# Power_5V_Rev1_1.net
KiCad netlist of a schematic drawn in Altium Designer
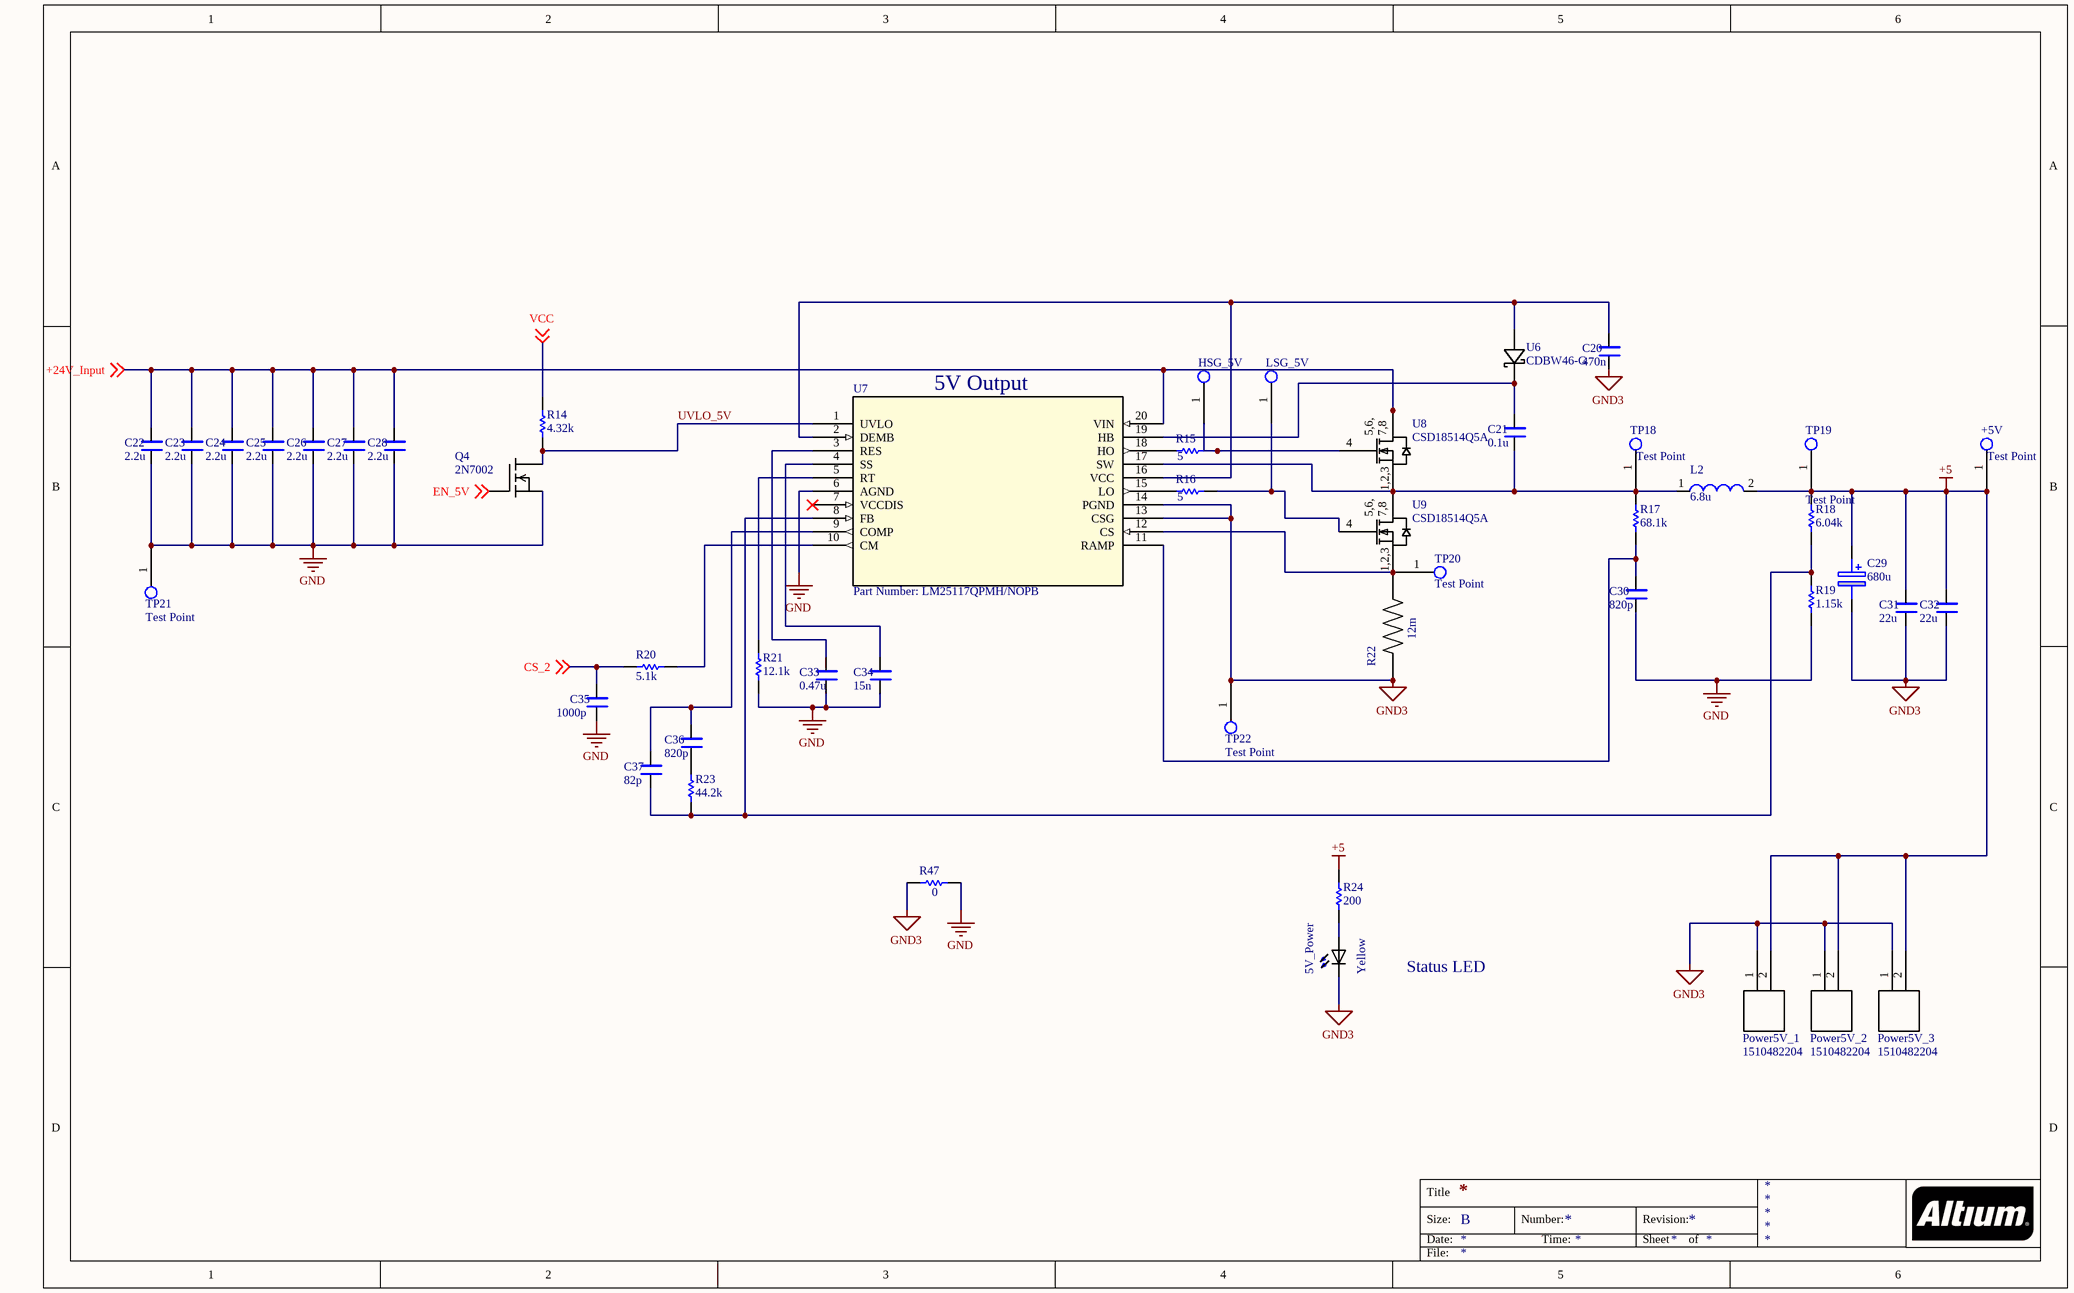
[diagram p0: Power_5V_Rev1.1.SchDoc]

(export (version "E")
  (design (tool "Eeschema 10.0.6"))
  (components
    (comp (ref "+5V")
      (value "Test Point")
      (footprint "Test Point Through-hole")
      (libsource (lib "Test Points") (part "Test Point"))
    )
    (comp (ref "5V_Power")
      (value "Yellow")
      (footprint "*DIOC200X125X110_LTST-C171KSKT(Primary)")
      (description "Yellow 2 x 1.25 x 0.8 mm 130Â° Water Clear 50 mcd 2 V LED SMT")
      (fields (field (name "MP") "LTST-C171KSKT") (field (name "DIGI-KEY_PART_NUMBER") "160-1428-1-ND"))
      (libsource (lib "LTST-C171KSKT") (part "LTST-C171KSKT"))
    )
    (comp (ref "C20")
      (value "470n")
      (footprint "*CAPC2012X88N")
      (description "100pF Â±5% 250V Ceramic Capacitor C0G, NP0 0805 _2012 Metric_")
      (fields (field (name "MF") "KEMET") (field (name "DIGI-KEY_PART_NUMBER") "399-15000-1-ND"))
      (libsource (lib "C0805C101JAGAC7800") (part "C0805C101JAGAC7800"))
    )
    (comp (ref "C21")
      (value "0.1u")
      (footprint "*CAPC2012X88N")
      (description "100pF Â±5% 250V Ceramic Capacitor C0G, NP0 0805 _2012 Metric_")
      (fields (field (name "MF") "KEMET") (field (name "DIGI-KEY_PART_NUMBER") "399-15000-1-ND"))
      (libsource (lib "C0805C101JAGAC7800") (part "C0805C101JAGAC7800"))
    )
    (comp (ref "C22")
      (value "2.2u")
      (footprint "*CAPC2012X88N")
      (description "100pF Â±5% 250V Ceramic Capacitor C0G, NP0 0805 _2012 Metric_")
      (fields (field (name "MF") "KEMET") (field (name "DIGI-KEY_PART_NUMBER") "399-15000-1-ND"))
      (libsource (lib "C0805C101JAGAC7800") (part "C0805C101JAGAC7800"))
    )
    (comp (ref "C23")
      (value "2.2u")
      (footprint "*CAPC2012X88N")
      (description "100pF Â±5% 250V Ceramic Capacitor C0G, NP0 0805 _2012 Metric_")
      (fields (field (name "MF") "KEMET") (field (name "DIGI-KEY_PART_NUMBER") "399-15000-1-ND"))
      (libsource (lib "C0805C101JAGAC7800") (part "C0805C101JAGAC7800"))
    )
    (comp (ref "C24")
      (value "2.2u")
      (footprint "*CAPC2012X88N")
      (description "100pF Â±5% 250V Ceramic Capacitor C0G, NP0 0805 _2012 Metric_")
      (fields (field (name "MF") "KEMET") (field (name "DIGI-KEY_PART_NUMBER") "399-15000-1-ND"))
      (libsource (lib "C0805C101JAGAC7800") (part "C0805C101JAGAC7800"))
    )
    (comp (ref "C25")
      (value "2.2u")
      (footprint "*CAPC2012X88N")
      (description "100pF Â±5% 250V Ceramic Capacitor C0G, NP0 0805 _2012 Metric_")
      (fields (field (name "MF") "KEMET") (field (name "DIGI-KEY_PART_NUMBER") "399-15000-1-ND"))
      (libsource (lib "C0805C101JAGAC7800") (part "C0805C101JAGAC7800"))
    )
    (comp (ref "C26")
      (value "2.2u")
      (footprint "*CAPC2012X88N")
      (description "100pF Â±5% 250V Ceramic Capacitor C0G, NP0 0805 _2012 Metric_")
      (fields (field (name "MF") "KEMET") (field (name "DIGI-KEY_PART_NUMBER") "399-15000-1-ND"))
      (libsource (lib "C0805C101JAGAC7800") (part "C0805C101JAGAC7800"))
    )
    (comp (ref "C27")
      (value "2.2u")
      (footprint "*CAPC2012X88N")
      (description "100pF Â±5% 250V Ceramic Capacitor C0G, NP0 0805 _2012 Metric_")
      (fields (field (name "MF") "KEMET") (field (name "DIGI-KEY_PART_NUMBER") "399-15000-1-ND"))
      (libsource (lib "C0805C101JAGAC7800") (part "C0805C101JAGAC7800"))
    )
    (comp (ref "C28")
      (value "2.2u")
      (footprint "*CAPC2012X88N")
      (description "100pF Â±5% 250V Ceramic Capacitor C0G, NP0 0805 _2012 Metric_")
      (fields (field (name "MF") "KEMET") (field (name "DIGI-KEY_PART_NUMBER") "399-15000-1-ND"))
      (libsource (lib "C0805C101JAGAC7800") (part "C0805C101JAGAC7800"))
    )
    (comp (ref "C29")
      (value "680u")
      (footprint "CAPPRD500W65D1000H1800")
      (fields
        (field (name "MANUFACTURER_PART_NUMBER") "EEUFC1V331")
        (field (name "RS PART NUMBER") "1081337")
      )
      (libsource (lib "Power Distribution") (part "EEUFC1V331"))
    )
    (comp (ref "C30")
      (value "820p")
      (footprint "*CAPC2012X88N")
      (description "100pF Â±5% 250V Ceramic Capacitor C0G, NP0 0805 _2012 Metric_")
      (fields (field (name "MF") "KEMET") (field (name "DIGI-KEY_PART_NUMBER") "399-15000-1-ND"))
      (libsource (lib "C0805C101JAGAC7800") (part "C0805C101JAGAC7800"))
    )
    (comp (ref "C31")
      (value "22u")
      (footprint "*CAPC2012X88N")
      (description "100pF Â±5% 250V Ceramic Capacitor C0G, NP0 0805 _2012 Metric_")
      (fields (field (name "MF") "KEMET") (field (name "DIGI-KEY_PART_NUMBER") "399-15000-1-ND"))
      (libsource (lib "C0805C101JAGAC7800") (part "C0805C101JAGAC7800"))
    )
    (comp (ref "C32")
      (value "22u")
      (footprint "*CAPC2012X88N")
      (description "100pF Â±5% 250V Ceramic Capacitor C0G, NP0 0805 _2012 Metric_")
      (fields (field (name "MF") "KEMET") (field (name "DIGI-KEY_PART_NUMBER") "399-15000-1-ND"))
      (libsource (lib "C0805C101JAGAC7800") (part "C0805C101JAGAC7800"))
    )
    (comp (ref "C33")
      (value "0.47u")
      (footprint "*CAPC2012X88N")
      (description "100pF Â±5% 250V Ceramic Capacitor C0G, NP0 0805 _2012 Metric_")
      (fields (field (name "MF") "KEMET") (field (name "DIGI-KEY_PART_NUMBER") "399-15000-1-ND"))
      (libsource (lib "C0805C101JAGAC7800") (part "C0805C101JAGAC7800"))
    )
    (comp (ref "C34")
      (value "15n")
      (footprint "*CAPC2012X88N")
      (description "100pF Â±5% 250V Ceramic Capacitor C0G, NP0 0805 _2012 Metric_")
      (fields (field (name "MF") "KEMET") (field (name "DIGI-KEY_PART_NUMBER") "399-15000-1-ND"))
      (libsource (lib "C0805C101JAGAC7800") (part "C0805C101JAGAC7800"))
    )
    (comp (ref "C35")
      (value "1000p")
      (footprint "*CAPC2012X88N")
      (description "100pF Â±5% 250V Ceramic Capacitor C0G, NP0 0805 _2012 Metric_")
      (fields (field (name "MF") "KEMET") (field (name "DIGI-KEY_PART_NUMBER") "399-15000-1-ND"))
      (libsource (lib "C0805C101JAGAC7800") (part "C0805C101JAGAC7800"))
    )
    (comp (ref "C36")
      (value "820p")
      (footprint "*CAPC2012X88N")
      (description "100pF Â±5% 250V Ceramic Capacitor C0G, NP0 0805 _2012 Metric_")
      (fields (field (name "MF") "KEMET") (field (name "DIGI-KEY_PART_NUMBER") "399-15000-1-ND"))
      (libsource (lib "C0805C101JAGAC7800") (part "C0805C101JAGAC7800"))
    )
    (comp (ref "C37")
      (value "82p")
      (footprint "*CAPC2012X88N")
      (description "100pF Â±5% 250V Ceramic Capacitor C0G, NP0 0805 _2012 Metric_")
      (fields (field (name "MF") "KEMET") (field (name "DIGI-KEY_PART_NUMBER") "399-15000-1-ND"))
      (libsource (lib "C0805C101JAGAC7800") (part "C0805C101JAGAC7800"))
    )
    (comp (ref "HSG_5V")
      (value "~")
      (footprint "Test Point Through-hole")
      (libsource (lib "Test Points") (part "Test Point"))
    )
    (comp (ref "L2")
      (value "6.8u")
      (footprint "XAL1010-682")
      (description "Power inductor, high current, 10% tol, SMT, RoHS")
      (fields (field (name "MF") "Coilcraft") (field (name "MP") "SER2915H-153KL"))
      (libsource (lib "SER2915H-153KL") (part "SER2915H-153KL"))
    )
    (comp (ref "LSG_5V")
      (value "~")
      (footprint "Test Point Through-hole")
      (libsource (lib "Test Points") (part "Test Point"))
    )
    (comp (ref "Power5V_1")
      (value "1510482204")
      (footprint "1510482204")
      (description "Molex 6.5MM 2 pin connector, used for power connections. P/N 1510482204 and similar models.")
      (libsource (lib "Power Distribution") (part "1510482204"))
    )
    (comp (ref "Power5V_2")
      (value "1510482204")
      (footprint "1510482204")
      (description "Molex 6.5MM 2 pin connector, used for power connections. P/N 1510482204 and similar models.")
      (libsource (lib "Power Distribution") (part "1510482204"))
    )
    (comp (ref "Power5V_3")
      (value "1510482204")
      (footprint "1510482204")
      (description "Molex 6.5MM 2 pin connector, used for power connections. P/N 1510482204 and similar models.")
      (libsource (lib "Power Distribution") (part "1510482204"))
    )
    (comp (ref "Q4")
      (value "2N7002")
      (footprint "*SOT23")
      (description "Trans MOSFET N-CH 60V 0.115A 3-Pin SOT-23 T/R")
      (fields (field (name "MF") "ON Semiconductor"))
      (libsource (lib "2N7002") (part "2N7002"))
    )
    (comp (ref "R14")
      (value "4.32k")
      (footprint "RESC0805(2012)_M")
      (description "8M06 0.125W 1% 0805 (2012 Metric)  SMD")
      (fields (field (name "POWER") "0.125 W") (field (name "TOLERANCE") "1 %"))
      (libsource (lib "Altium Content Vault") (part "RES"))
    )
    (comp (ref "R15")
      (value "5")
      (footprint "AXIAL-0.3")
      (description "120R 0.125W 5% 0805 (2012 Metric)  SMD")
      (fields (field (name "TOLERANCE") "5 %") (field (name "POWER") "0.125 W"))
      (libsource (lib "Power Distribution") (part "120R 5% 0805"))
    )
    (comp (ref "R16")
      (value "5")
      (footprint "AXIAL-0.3")
      (description "120R 0.125W 5% 0805 (2012 Metric)  SMD")
      (fields (field (name "TOLERANCE") "5 %") (field (name "POWER") "0.125 W"))
      (libsource (lib "Power Distribution") (part "120R 5% 0805"))
    )
    (comp (ref "R17")
      (value "68.1k")
      (footprint "RESC0805(2012)_M")
      (description "8M06 0.125W 1% 0805 (2012 Metric)  SMD")
      (fields (field (name "POWER") "0.125 W") (field (name "TOLERANCE") "1 %"))
      (libsource (lib "Altium Content Vault") (part "RES"))
    )
    (comp (ref "R18")
      (value "6.04k")
      (footprint "RESC0805(2012)_M")
      (description "8M06 0.125W 1% 0805 (2012 Metric)  SMD")
      (fields (field (name "POWER") "0.125 W") (field (name "TOLERANCE") "1 %"))
      (libsource (lib "Altium Content Vault") (part "RES"))
    )
    (comp (ref "R19")
      (value "1.15k")
      (footprint "RESC0805(2012)_M")
      (description "8M06 0.125W 1% 0805 (2012 Metric)  SMD")
      (fields (field (name "POWER") "0.125 W") (field (name "TOLERANCE") "1 %"))
      (libsource (lib "Altium Content Vault") (part "RES"))
    )
    (comp (ref "R20")
      (value "5.1k")
      (footprint "RESC0805(2012)_M")
      (description "8M06 0.125W 1% 0805 (2012 Metric)  SMD")
      (fields (field (name "POWER") "0.125 W") (field (name "TOLERANCE") "1 %"))
      (libsource (lib "Altium Content Vault") (part "RES"))
    )
    (comp (ref "R21")
      (value "12.1k")
      (footprint "RESC0805(2012)_M")
      (description "8M06 0.125W 1% 0805 (2012 Metric)  SMD")
      (fields (field (name "POWER") "0.125 W") (field (name "TOLERANCE") "1 %"))
      (libsource (lib "Altium Content Vault") (part "RES"))
    )
    (comp (ref "R22")
      (value "12m")
      (footprint "*RESC6432X110N")
      (description "Res Thick Film 2512 0.012 Ohm 1% 1W Pad SMD Automotive T/R")
      (fields (field (name "MP") "ERJ-M1WSF12MU") (field (name "DIGI-KEY_PART_NUMBER") "P12MCT-ND"))
      (libsource (lib "ERJ-M1WSF12MU") (part "ERJ-M1WSF12MU"))
    )
    (comp (ref "R23")
      (value "44.2k")
      (footprint "RESC0805(2012)_M")
      (description "8M06 0.125W 1% 0805 (2012 Metric)  SMD")
      (fields (field (name "POWER") "0.125 W") (field (name "TOLERANCE") "1 %"))
      (libsource (lib "Altium Content Vault") (part "RES"))
    )
    (comp (ref "R24")
      (value "200")
      (footprint "RESC0805(2012)_M")
      (description "8M06 0.125W 1% 0805 (2012 Metric)  SMD")
      (fields (field (name "POWER") "0.125 W") (field (name "TOLERANCE") "1 %"))
      (libsource (lib "Altium Content Vault") (part "RES"))
    )
    (comp (ref "R47")
      (value "0")
      (footprint "RESC0805(2012)_M")
      (description "8M06 0.125W 1% 0805 (2012 Metric)  SMD")
      (fields (field (name "POWER") "0.125 W") (field (name "TOLERANCE") "1 %"))
      (libsource (lib "Altium Content Vault") (part "RES"))
    )
    (comp (ref "TP18")
      (value "Test Point")
      (footprint "Test Point Through-hole")
      (libsource (lib "Test Points") (part "Test Point"))
    )
    (comp (ref "TP19")
      (value "Test Point")
      (footprint "Test Point Through-hole")
      (libsource (lib "Test Points") (part "Test Point"))
    )
    (comp (ref "TP20")
      (value "Test Point")
      (footprint "Test Point Through-hole")
      (libsource (lib "Test Points") (part "Test Point"))
    )
    (comp (ref "TP21")
      (value "Test Point")
      (footprint "Test Point Through-hole")
      (libsource (lib "Test Points") (part "Test Point"))
    )
    (comp (ref "TP22")
      (value "Test Point")
      (footprint "Test Point Through-hole")
      (libsource (lib "Test Points") (part "Test Point"))
    )
    (comp (ref "U6")
      (value "CDBW46-G")
      (footprint "CDBW")
      (description "No Description Available")
      (fields (field (name "COPYRIGHT") "Copyright (C) 2018 Accelerated Designs. All rights reserved"))
      (libsource (lib "DIODE SCHOTTKY 100V 150MA") (part "CDBW46-G"))
    )
    (comp (ref "U7")
      (value "Part Number: LM25117QPMH/NOPB")
      (footprint "MXA20A")
      (description "No Description Available")
      (fields
        (field (name "MANUFACTURER") "Texas Instruments")
        (field (name "MANUFACTURER_PART_NUMBER") "LM25117QPMH/NOPB")
        (field (name "COPYRIGHT") "Copyright (C) 2018 Accelerated Designs. All rights reserved")
      )
      (libsource (lib "2019-11-16_22-35-15") (part "LM25117QPMH/NOPB"))
    )
    (comp (ref "U8")
      (value "CSD18514Q5A")
      (footprint "DQJ0008A")
      (description "No Description Available")
      (fields (field (name "COPYRIGHT") "Copyright (C) 2018 Accelerated Designs. All rights reserved"))
      (libsource (lib "ul_CSD18514Q5A") (part "CSD18514Q5A"))
    )
    (comp (ref "U9")
      (value "CSD18514Q5A")
      (footprint "DQJ0008A")
      (description "No Description Available")
      (fields (field (name "COPYRIGHT") "Copyright (C) 2018 Accelerated Designs. All rights reserved"))
      (libsource (lib "ul_CSD18514Q5A") (part "CSD18514Q5A"))
    )
  )
  (nets
    (net (code "1") (name "+5") (class "Default")
      (node (ref "+5V") (pin "1") (pinfunction "1_1") (pintype "passive"))
      (node (ref "C29") (pin "1") (pinfunction "+_1") (pintype "passive"))
      (node (ref "C31") (pin "2") (pinfunction "2_2") (pintype "passive"))
      (node (ref "C32") (pin "2") (pinfunction "2_2") (pintype "passive"))
      (node (ref "L2") (pin "2") (pinfunction "2_2") (pintype "passive"))
      (node (ref "Power5V_1") (pin "2") (pintype "passive"))
      (node (ref "Power5V_2") (pin "2") (pintype "passive"))
      (node (ref "Power5V_3") (pin "2") (pintype "passive"))
      (node (ref "R18") (pin "2") (pinfunction "2_2") (pintype "passive"))
      (node (ref "R24") (pin "2") (pinfunction "2_2") (pintype "passive"))
      (node (ref "TP19") (pin "1") (pinfunction "1_1") (pintype "passive"))
    )
    (net (code "2") (name "+24V_Input") (class "Default")
      (node (ref "C22") (pin "2") (pinfunction "2_2") (pintype "passive"))
      (node (ref "C23") (pin "2") (pinfunction "2_2") (pintype "passive"))
      (node (ref "C24") (pin "2") (pinfunction "2_2") (pintype "passive"))
      (node (ref "C25") (pin "2") (pinfunction "2_2") (pintype "passive"))
      (node (ref "C26") (pin "2") (pinfunction "2_2") (pintype "passive"))
      (node (ref "C27") (pin "2") (pinfunction "2_2") (pintype "passive"))
      (node (ref "C28") (pin "2") (pinfunction "2_2") (pintype "passive"))
      (node (ref "U7") (pin "20") (pinfunction "VIN_20") (pintype "input"))
      (node (ref "U8") (pin "5") (pinfunction "D_5") (pintype "passive"))
      (node (ref "U8") (pin "6") (pinfunction "D_6") (pintype "passive"))
      (node (ref "U8") (pin "7") (pinfunction "D_7") (pintype "passive"))
      (node (ref "U8") (pin "8") (pinfunction "D_8") (pintype "passive"))
    )
    (net (code "3") (name "/UVLO_5V") (class "Default")
      (node (ref "Q4") (pin "3") (pinfunction "D_3") (pintype "passive"))
      (node (ref "R14") (pin "1") (pinfunction "1_1") (pintype "passive"))
      (node (ref "U7") (pin "1") (pinfunction "UVLO_1") (pintype "passive"))
    )
    (net (code "4") (name "CS_2") (class "Default")
      (node (ref "C35") (pin "2") (pinfunction "2_2") (pintype "passive"))
      (node (ref "R20") (pin "2") (pinfunction "2_2") (pintype "passive"))
    )
    (net (code "5") (name "EN_5V") (class "Default")
      (node (ref "Q4") (pin "1") (pinfunction "G_1") (pintype "passive"))
    )
    (net (code "6") (name "GND") (class "Default")
      (node (ref "C22") (pin "1") (pinfunction "1_1") (pintype "passive"))
      (node (ref "C23") (pin "1") (pinfunction "1_1") (pintype "passive"))
      (node (ref "C24") (pin "1") (pinfunction "1_1") (pintype "passive"))
      (node (ref "C25") (pin "1") (pinfunction "1_1") (pintype "passive"))
      (node (ref "C26") (pin "1") (pinfunction "1_1") (pintype "passive"))
      (node (ref "C27") (pin "1") (pinfunction "1_1") (pintype "passive"))
      (node (ref "C28") (pin "1") (pinfunction "1_1") (pintype "passive"))
      (node (ref "C30") (pin "1") (pinfunction "1_1") (pintype "passive"))
      (node (ref "C33") (pin "1") (pinfunction "1_1") (pintype "passive"))
      (node (ref "C34") (pin "1") (pinfunction "1_1") (pintype "passive"))
      (node (ref "C35") (pin "1") (pinfunction "1_1") (pintype "passive"))
      (node (ref "Q4") (pin "2") (pinfunction "S_2") (pintype "passive"))
      (node (ref "R19") (pin "1") (pinfunction "1_1") (pintype "passive"))
      (node (ref "R21") (pin "1") (pinfunction "1_1") (pintype "passive"))
      (node (ref "R47") (pin "1") (pinfunction "1_1") (pintype "passive"))
      (node (ref "TP21") (pin "1") (pinfunction "1_1") (pintype "passive"))
      (node (ref "U7") (pin "6") (pinfunction "AGND_6") (pintype "power_in"))
    )
    (net (code "7") (name "GND3") (class "Default")
      (node (ref "5V_Power") (pin "NEG") (pinfunction "NEG_NEG") (pintype "passive"))
      (node (ref "C20") (pin "1") (pinfunction "1_1") (pintype "passive"))
      (node (ref "C29") (pin "2") (pinfunction "-_2") (pintype "passive"))
      (node (ref "C31") (pin "1") (pinfunction "1_1") (pintype "passive"))
      (node (ref "C32") (pin "1") (pinfunction "1_1") (pintype "passive"))
      (node (ref "Power5V_1") (pin "1") (pintype "passive"))
      (node (ref "Power5V_2") (pin "1") (pintype "passive"))
      (node (ref "Power5V_3") (pin "1") (pintype "passive"))
      (node (ref "R22") (pin "1") (pinfunction "1_1") (pintype "passive"))
      (node (ref "R47") (pin "2") (pinfunction "2_2") (pintype "passive"))
      (node (ref "TP22") (pin "1") (pinfunction "1_1") (pintype "passive"))
      (node (ref "U7") (pin "13") (pinfunction "CSG_13") (pintype "passive"))
      (node (ref "U7") (pin "14") (pinfunction "PGND_14") (pintype "power_in"))
    )
    (net (code "8") (name "Net-(5V_Power-PadPOS)") (class "Default")
      (node (ref "5V_Power") (pin "POS") (pinfunction "POS_POS") (pintype "passive"))
      (node (ref "R24") (pin "1") (pinfunction "1_1") (pintype "passive"))
    )
    (net (code "9") (name "Net-(C36-Pad1)") (class "Default")
      (node (ref "C36") (pin "1") (pinfunction "1_1") (pintype "passive"))
      (node (ref "R23") (pin "2") (pinfunction "2_2") (pintype "passive"))
    )
    (net (code "10") (name "Net-(U7-CM)") (class "Default")
      (node (ref "R20") (pin "1") (pinfunction "1_1") (pintype "passive"))
      (node (ref "U7") (pin "10") (pinfunction "CM_10") (pintype "output"))
    )
    (net (code "11") (name "Net-(U7-COMP)") (class "Default")
      (node (ref "C36") (pin "2") (pinfunction "2_2") (pintype "passive"))
      (node (ref "C37") (pin "2") (pinfunction "2_2") (pintype "passive"))
      (node (ref "U7") (pin "9") (pinfunction "COMP_9") (pintype "output"))
    )
    (net (code "12") (name "Net-(U7-CS)") (class "Default")
      (node (ref "R22") (pin "2") (pinfunction "2_2") (pintype "passive"))
      (node (ref "TP20") (pin "1") (pinfunction "1_1") (pintype "passive"))
      (node (ref "U7") (pin "12") (pinfunction "CS_12") (pintype "input"))
      (node (ref "U9") (pin "1") (pinfunction "S_1") (pintype "passive"))
      (node (ref "U9") (pin "2") (pinfunction "S_2") (pintype "passive"))
      (node (ref "U9") (pin "3") (pinfunction "S_3") (pintype "passive"))
    )
    (net (code "13") (name "Net-(U7-DEMB)") (class "Default")
      (node (ref "C20") (pin "2") (pinfunction "2_2") (pintype "passive"))
      (node (ref "U6") (pin "2") (pinfunction "2_2") (pintype "passive"))
      (node (ref "U7") (pin "16") (pinfunction "VCC_16") (pintype "power_in"))
      (node (ref "U7") (pin "2") (pinfunction "DEMB_2") (pintype "input"))
    )
    (net (code "14") (name "Net-(U7-FB)") (class "Default")
      (node (ref "C37") (pin "1") (pinfunction "1_1") (pintype "passive"))
      (node (ref "R18") (pin "1") (pinfunction "1_1") (pintype "passive"))
      (node (ref "R19") (pin "2") (pinfunction "2_2") (pintype "passive"))
      (node (ref "R23") (pin "1") (pinfunction "1_1") (pintype "passive"))
      (node (ref "U7") (pin "8") (pinfunction "FB_8") (pintype "input"))
    )
    (net (code "15") (name "Net-(U7-HB)") (class "Default")
      (node (ref "C21") (pin "2") (pinfunction "2_2") (pintype "passive"))
      (node (ref "U6") (pin "1") (pinfunction "1_1") (pintype "passive"))
      (node (ref "U7") (pin "19") (pinfunction "HB_19") (pintype "passive"))
    )
    (net (code "16") (name "Net-(U7-HO)") (class "Default")
      (node (ref "R15") (pin "1") (pinfunction "1_1") (pintype "passive"))
      (node (ref "U7") (pin "18") (pinfunction "HO_18") (pintype "output"))
    )
    (net (code "17") (name "Net-(U7-LO)") (class "Default")
      (node (ref "R16") (pin "1") (pinfunction "1_1") (pintype "passive"))
      (node (ref "U7") (pin "15") (pinfunction "LO_15") (pintype "output"))
    )
    (net (code "18") (name "Net-(U7-RAMP)") (class "Default")
      (node (ref "C30") (pin "2") (pinfunction "2_2") (pintype "passive"))
      (node (ref "R17") (pin "1") (pinfunction "1_1") (pintype "passive"))
      (node (ref "U7") (pin "11") (pinfunction "RAMP_11") (pintype "passive"))
    )
    (net (code "19") (name "Net-(U7-RES)") (class "Default")
      (node (ref "C33") (pin "2") (pinfunction "2_2") (pintype "passive"))
      (node (ref "U7") (pin "3") (pinfunction "RES_3") (pintype "passive"))
    )
    (net (code "20") (name "Net-(U7-RT)") (class "Default")
      (node (ref "R21") (pin "2") (pinfunction "2_2") (pintype "passive"))
      (node (ref "U7") (pin "5") (pinfunction "RT_5") (pintype "passive"))
    )
    (net (code "21") (name "Net-(U7-SS)") (class "Default")
      (node (ref "C34") (pin "2") (pinfunction "2_2") (pintype "passive"))
      (node (ref "U7") (pin "4") (pinfunction "SS_4") (pintype "passive"))
    )
    (net (code "22") (name "Net-(U7-SW)") (class "Default")
      (node (ref "C21") (pin "1") (pinfunction "1_1") (pintype "passive"))
      (node (ref "L2") (pin "1") (pinfunction "1_1") (pintype "passive"))
      (node (ref "R17") (pin "2") (pinfunction "2_2") (pintype "passive"))
      (node (ref "TP18") (pin "1") (pinfunction "1_1") (pintype "passive"))
      (node (ref "U7") (pin "17") (pinfunction "SW_17") (pintype "passive"))
      (node (ref "U8") (pin "1") (pinfunction "S_1") (pintype "passive"))
      (node (ref "U8") (pin "2") (pinfunction "S_2") (pintype "passive"))
      (node (ref "U8") (pin "3") (pinfunction "S_3") (pintype "passive"))
      (node (ref "U9") (pin "5") (pinfunction "D_5") (pintype "passive"))
      (node (ref "U9") (pin "6") (pinfunction "D_6") (pintype "passive"))
      (node (ref "U9") (pin "7") (pinfunction "D_7") (pintype "passive"))
      (node (ref "U9") (pin "8") (pinfunction "D_8") (pintype "passive"))
    )
    (net (code "23") (name "Net-(U8-G)") (class "Default")
      (node (ref "HSG_5V") (pin "1") (pinfunction "1_1") (pintype "passive"))
      (node (ref "R15") (pin "2") (pinfunction "2_2") (pintype "passive"))
      (node (ref "U8") (pin "4") (pinfunction "G_4") (pintype "passive"))
    )
    (net (code "24") (name "Net-(U9-G)") (class "Default")
      (node (ref "LSG_5V") (pin "1") (pinfunction "1_1") (pintype "passive"))
      (node (ref "R16") (pin "2") (pinfunction "2_2") (pintype "passive"))
      (node (ref "U9") (pin "4") (pinfunction "G_4") (pintype "passive"))
    )
    (net (code "25") (name "VCC") (class "Default")
      (node (ref "R14") (pin "2") (pinfunction "2_2") (pintype "passive"))
    )
    (net (code "26") (name "unconnected-(U7-VCCDIS-Pad7)") (class "Default")
      (node (ref "U7") (pin "7") (pinfunction "VCCDIS_7") (pintype "input+no_connect"))
    )
  )
)
